# StepStick_Driver.net
KiCad netlist of a schematic drawn in Altium Designer
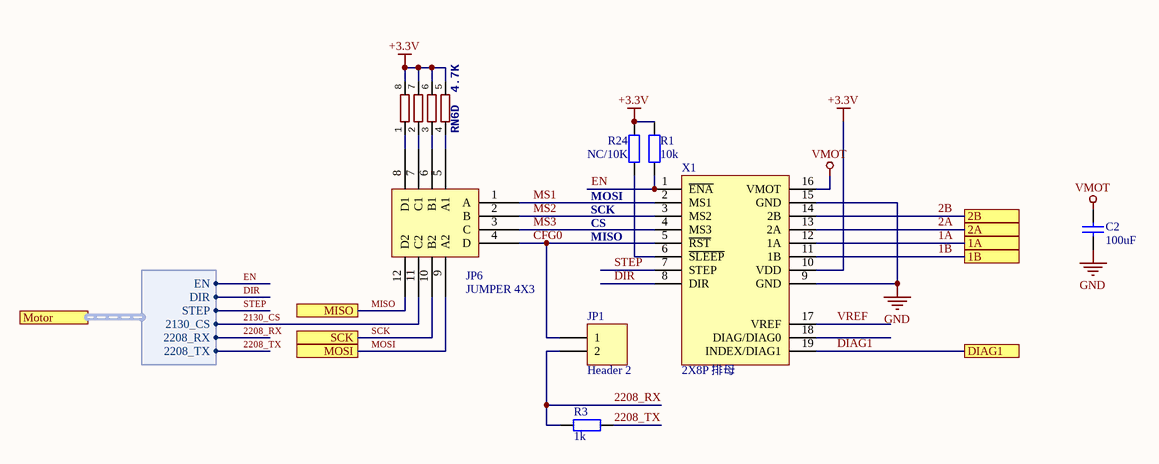
[diagram p0: StepStick_Driver.SchDoc]

(export (version "E")
  (design (tool "Eeschema 10.0.6"))
  (components
    (comp (ref "C2") (value "100uF") (footprint "ELCO Case D") (libsource (lib "接插件库") (part "Capacitor")))
    (comp (ref "JP1")
      (value "Header 2")
      (footprint "HDR1X2")
      (description "Header, 2-Pin")
      (fields (field (name "PUBLISHER") "Altium Limited"))
      (libsource (lib "Miscellaneous Connectors") (part "Header 2"))
    )
    (comp (ref "JP6")
      (value "JUMPER 4X3")
      (footprint "HEADER 3x4")
      (libsource (lib "接插件库") (part "JUMPER 4X3"))
    )
    (comp (ref "R1")
      (value "10k")
      (footprint "RES0603")
      (description "RO RES 1k0 1% 0,1W  0603")
      (libsource (lib "Ultimaker2") (part "Resistor_2"))
    )
    (comp (ref "R3")
      (value "1k")
      (footprint "RES0402")
      (description "RO RES 1k0 1% 0,1W  0603")
      (libsource (lib "") (part "Resistor_2_1"))
    )
    (comp (ref "R24")
      (value "NC/10K")
      (footprint "RES0603")
      (description "RO RES 1k0 1% 0,1W  0603")
      (libsource (lib "Ultimaker2") (part "Resistor_2"))
    )
    (comp (ref "RN6")
      (value "4.7K")
      (footprint "RESISTOR-DIL_CAY16")
      (libsource (lib "接插件库") (part "RESISTOR-DIL_4R-NCAY16"))
    )
    (comp (ref "X1")
      (value "2X8P 排母")
      (footprint "TMC_breakout")
      (libsource (lib "接插件库") (part "TMC_BREAKOUT"))
    )
  )
  (nets
    (net (code "2") (name "+3.3V") (class "Default")
      (node (ref "R1") (pin "2") (pinfunction "2_2") (pintype "passive"))
      (node (ref "R24") (pin "2") (pinfunction "2_2") (pintype "passive"))
      (node (ref "RN6") (pin "5") (pinfunction "2_5") (pintype "passive"))
      (node (ref "RN6") (pin "6") (pinfunction "2_6") (pintype "passive"))
      (node (ref "RN6") (pin "7") (pinfunction "2_7") (pintype "passive"))
      (node (ref "RN6") (pin "8") (pinfunction "2_8") (pintype "passive"))
      (node (ref "X1") (pin "10") (pinfunction "VDD_10") (pintype "passive"))
    )
    (net (code "3") (name "/1A") (class "Default")
      (node (ref "X1") (pin "12") (pinfunction "1A_12") (pintype "passive"))
    )
    (net (code "4") (name "/1B") (class "Default")
      (node (ref "X1") (pin "11") (pinfunction "1B_11") (pintype "passive"))
    )
    (net (code "5") (name "/2A") (class "Default")
      (node (ref "X1") (pin "13") (pinfunction "2A_13") (pintype "passive"))
    )
    (net (code "6") (name "/2B") (class "Default")
      (node (ref "X1") (pin "14") (pinfunction "2B_14") (pintype "passive"))
    )
    (net (code "7") (name "/2130_CS") (class "Default")
      (node (ref "JP6") (pin "11") (pinfunction "C2_11") (pintype "passive"))
    )
    (net (code "8") (name "/2208_RX") (class "Default")
      (node (ref "JP1") (pin "2") (pinfunction "2_2") (pintype "passive"))
      (node (ref "R3") (pin "1") (pinfunction "1_1") (pintype "passive"))
    )
    (net (code "9") (name "/2208_TX") (class "Default")
      (node (ref "R3") (pin "2") (pinfunction "2_2") (pintype "passive"))
    )
    (net (code "10") (name "/CFG0") (class "Default")
      (node (ref "JP1") (pin "1") (pinfunction "1_1") (pintype "passive"))
      (node (ref "JP6") (pin "4") (pinfunction "D_4") (pintype "passive"))
      (node (ref "X1") (pin "5") (pinfunction "~{RST}_5") (pintype "passive"))
    )
    (net (code "11") (name "/DIAG1") (class "Default")
      (node (ref "X1") (pin "19") (pinfunction "INDEX/DIAG1_19") (pintype "passive"))
    )
    (net (code "12") (name "/DIR") (class "Default")
      (node (ref "X1") (pin "8") (pinfunction "DIR_8") (pintype "passive"))
    )
    (net (code "13") (name "/EN") (class "Default")
      (node (ref "R1") (pin "1") (pinfunction "1_1") (pintype "passive"))
      (node (ref "X1") (pin "1") (pinfunction "~{ENA}_1") (pintype "passive"))
    )
    (net (code "14") (name "/MISO") (class "Default")
      (node (ref "JP6") (pin "12") (pinfunction "D2_12") (pintype "passive"))
    )
    (net (code "15") (name "/MOSI") (class "Default")
      (node (ref "JP6") (pin "9") (pinfunction "A2_9") (pintype "passive"))
    )
    (net (code "16") (name "/MS1") (class "Default")
      (node (ref "JP6") (pin "1") (pinfunction "A_1") (pintype "passive"))
      (node (ref "X1") (pin "2") (pinfunction "MS1_2") (pintype "passive"))
    )
    (net (code "17") (name "/MS2") (class "Default")
      (node (ref "JP6") (pin "2") (pinfunction "B_2") (pintype "passive"))
      (node (ref "X1") (pin "3") (pinfunction "MS2_3") (pintype "passive"))
    )
    (net (code "18") (name "/MS3") (class "Default")
      (node (ref "JP6") (pin "3") (pinfunction "C_3") (pintype "passive"))
      (node (ref "X1") (pin "4") (pinfunction "MS3_4") (pintype "passive"))
    )
    (net (code "19") (name "/SCK") (class "Default")
      (node (ref "JP6") (pin "10") (pinfunction "B2_10") (pintype "passive"))
    )
    (net (code "20") (name "/STEP") (class "Default")
      (node (ref "X1") (pin "7") (pinfunction "STEP_7") (pintype "passive"))
    )
    (net (code "21") (name "/VREF") (class "Default")
      (node (ref "X1") (pin "17") (pinfunction "VREF_17") (pintype "passive"))
    )
    (net (code "23") (name "GND") (class "Default")
      (node (ref "C2") (pin "2") (pinfunction "2_2") (pintype "passive"))
      (node (ref "X1") (pin "15") (pinfunction "GND_15") (pintype "passive"))
      (node (ref "X1") (pin "9") (pinfunction "GND_9") (pintype "passive"))
    )
    (net (code "24") (name "Net-(JP6-A1)") (class "Default")
      (node (ref "JP6") (pin "5") (pinfunction "A1_5") (pintype "passive"))
      (node (ref "RN6") (pin "4") (pinfunction "1_4") (pintype "passive"))
    )
    (net (code "25") (name "Net-(JP6-B1)") (class "Default")
      (node (ref "JP6") (pin "6") (pinfunction "B1_6") (pintype "passive"))
      (node (ref "RN6") (pin "3") (pinfunction "1_3") (pintype "passive"))
    )
    (net (code "26") (name "Net-(JP6-C1)") (class "Default")
      (node (ref "JP6") (pin "7") (pinfunction "C1_7") (pintype "passive"))
      (node (ref "RN6") (pin "2") (pinfunction "1_2") (pintype "passive"))
    )
    (net (code "27") (name "Net-(JP6-D1)") (class "Default")
      (node (ref "JP6") (pin "8") (pinfunction "D1_8") (pintype "passive"))
      (node (ref "RN6") (pin "1") (pinfunction "1_1") (pintype "passive"))
    )
    (net (code "28") (name "Net-(X1-~{SLEEP})") (class "Default")
      (node (ref "R24") (pin "1") (pinfunction "1_1") (pintype "passive"))
      (node (ref "X1") (pin "6") (pinfunction "~{SLEEP}_6") (pintype "passive"))
    )
    (net (code "29") (name "VMOT") (class "Default")
      (node (ref "C2") (pin "1") (pinfunction "1_1") (pintype "passive"))
      (node (ref "X1") (pin "16") (pinfunction "VMOT_16") (pintype "passive"))
    )
    (net (code "30") (name "unconnected-(X1-DIAG{slash}DIAG0-Pad18)") (class "Default")
      (node (ref "X1") (pin "18") (pinfunction "DIAG/DIAG0_18") (pintype "passive"))
    )
  )
)
